# kitt_db01.net
KiCad netlist of a schematic drawn in EAGLE
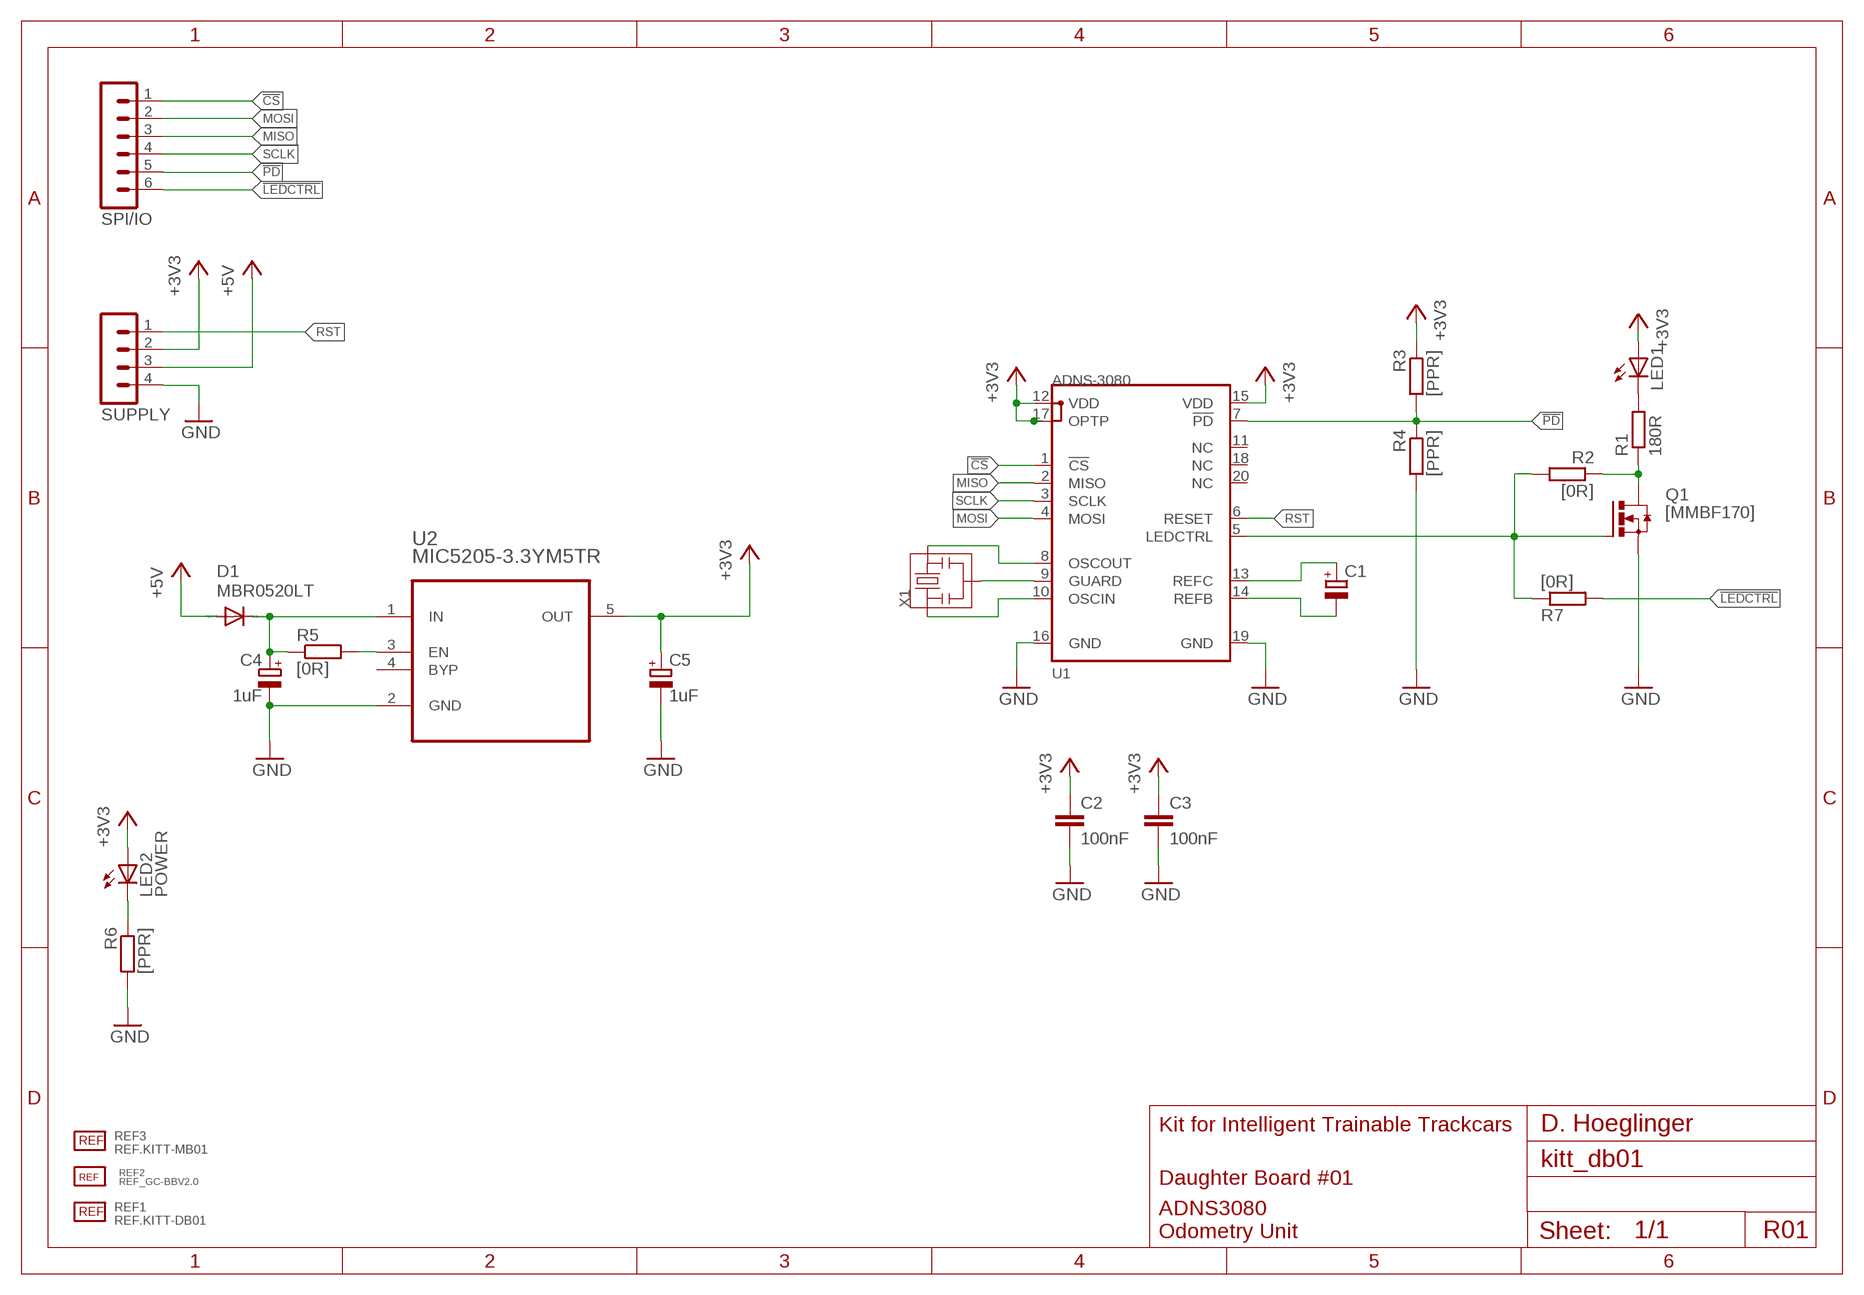
[diagram p0: schematic, sheet 1]

(export (version "E")
  (design (tool "Eeschema 10.0.6"))
  (components
    (comp (ref "C1")
      (value "CPOL-EUSMCB")
      (footprint "eagle-import:SMC_B")
      (libsource (lib "eagle-import") (part "CPOL-EUSMCB"))
    )
    (comp (ref "C2")
      (value "100nF")
      (footprint "eagle-import:C0805K")
      (libsource (lib "eagle-import") (part "C-EUC0805K"))
    )
    (comp (ref "C3")
      (value "100nF")
      (footprint "eagle-import:C0805K")
      (libsource (lib "eagle-import") (part "C-EUC0805K"))
    )
    (comp (ref "C4")
      (value "1uF")
      (footprint "eagle-import:A_3216-18W")
      (libsource (lib "eagle-import") (part "CPOL-EUA/3216-18W"))
    )
    (comp (ref "C5")
      (value "1uF")
      (footprint "eagle-import:A_3216-18W")
      (libsource (lib "eagle-import") (part "CPOL-EUA/3216-18W"))
    )
    (comp (ref "D1")
      (value "MBR0520LT")
      (footprint "eagle-import:SOD123")
      (libsource (lib "eagle-import") (part "MBR0520LT"))
    )
    (comp (ref "LED1")
      (value "LED5MM")
      (footprint "eagle-import:LED5MM")
      (libsource (lib "eagle-import") (part "LED5MM"))
    )
    (comp (ref "LED2")
      (value "POWER")
      (footprint "eagle-import:CHIP-LED0805")
      (libsource (lib "eagle-import") (part "LEDCHIP-LED0805"))
    )
    (comp (ref "Q1")
      (value "[MMBF170]")
      (footprint "eagle-import:SOT223")
      (libsource (lib "eagle-import") (part "N-HEXFET-2D_?-SOT232"))
    )
    (comp (ref "R1")
      (value "180R")
      (footprint "eagle-import:R0805")
      (libsource (lib "eagle-import") (part "R-EU_R0805"))
    )
    (comp (ref "R2")
      (value "[0R]")
      (footprint "eagle-import:R0805")
      (libsource (lib "eagle-import") (part "R-EU_R0805"))
    )
    (comp (ref "R3")
      (value "[PPR]")
      (footprint "eagle-import:R0805")
      (libsource (lib "eagle-import") (part "R-EU_R0805"))
    )
    (comp (ref "R4")
      (value "[PPR]")
      (footprint "eagle-import:R0805")
      (libsource (lib "eagle-import") (part "R-EU_R0805"))
    )
    (comp (ref "R5")
      (value "[0R]")
      (footprint "eagle-import:R0805")
      (libsource (lib "eagle-import") (part "R-EU_R0805"))
    )
    (comp (ref "R6")
      (value "[PPR]")
      (footprint "eagle-import:R0805")
      (libsource (lib "eagle-import") (part "R-EU_R0805"))
    )
    (comp (ref "R7")
      (value "[0R]")
      (footprint "eagle-import:R0805")
      (libsource (lib "eagle-import") (part "R-EU_R0805"))
    )
    (comp (ref "REF1")
      (value "REF.KITT-DB01")
      (footprint "eagle-import:REF_KITT-DB01")
      (libsource (lib "eagle-import") (part "REF.KITT-DB01"))
    )
    (comp (ref "REF2")
      (value "REF_GC-BBV2.0")
      (footprint "eagle-import:REF_GHOSTCAR")
      (libsource (lib "eagle-import") (part "REF_GC-BBV2.0"))
    )
    (comp (ref "REF3")
      (value "REF.KITT-MB01")
      (footprint "eagle-import:REF_KITT_MB01")
      (libsource (lib "eagle-import") (part "REF.KITT-MB01"))
    )
    (comp (ref "SPI/IO")
      (value "MA06-1")
      (footprint "eagle-import:MA06-1")
      (libsource (lib "eagle-import") (part "MA06-1"))
    )
    (comp (ref "SUPPLY")
      (value "MA04-1")
      (footprint "eagle-import:MA04-1")
      (libsource (lib "eagle-import") (part "MA04-1"))
    )
    (comp (ref "U1")
      (value "ADNS-3080")
      (footprint "eagle-import:ADNS-3080")
      (libsource (lib "eagle-import") (part "ADNS-3080"))
    )
    (comp (ref "U2")
      (value "MIC5205-3.3YM5TR")
      (footprint "eagle-import:SOT95P280X130-5N")
      (fields (field (name "MF") "Microchip") (field (name "MP") "MIC5205-3.3YM5-TR"))
      (libsource (lib "eagle-import") (part "MIC5205-3.3YM5TR"))
    )
    (comp (ref "X1")
      (value "RESON")
      (footprint "eagle-import:RESON-SMD")
      (libsource (lib "eagle-import") (part "RESON"))
    )
  )
  (nets
    (net (code "1") (name "+3V3") (class "Default")
      (node (ref "C2") (pin "1") (pinfunction "1_1") (pintype "passive"))
      (node (ref "C3") (pin "1") (pinfunction "1_1") (pintype "passive"))
      (node (ref "C5") (pin "+") (pinfunction "+_+") (pintype "passive"))
      (node (ref "LED1") (pin "A") (pinfunction "A_A") (pintype "passive"))
      (node (ref "LED2") (pin "A") (pinfunction "A_A") (pintype "passive"))
      (node (ref "R3") (pin "1") (pinfunction "1_1") (pintype "passive"))
      (node (ref "SUPPLY") (pin "2") (pinfunction "2_2") (pintype "passive"))
      (node (ref "U1") (pin "12") (pinfunction "VDD_12") (pintype "power_in"))
      (node (ref "U1") (pin "15") (pinfunction "VDD_15") (pintype "power_in"))
      (node (ref "U1") (pin "17") (pinfunction "OPTP_17") (pintype "open_collector"))
      (node (ref "U2") (pin "5") (pinfunction "OUT_5") (pintype "output"))
    )
    (net (code "2") (name "+5V") (class "Default")
      (node (ref "D1") (pin "A") (pinfunction "A_A") (pintype "passive"))
      (node (ref "SUPPLY") (pin "3") (pinfunction "3_3") (pintype "passive"))
    )
    (net (code "3") (name "/~{CS}") (class "Default")
      (node (ref "SPI/IO") (pin "1") (pinfunction "1_1") (pintype "passive"))
      (node (ref "U1") (pin "1") (pinfunction "~{CS}_1") (pintype "input"))
    )
    (net (code "4") (name "/~{LEDCTRL}") (class "Default")
      (node (ref "R7") (pin "2") (pinfunction "2_2") (pintype "passive"))
      (node (ref "SPI/IO") (pin "6") (pinfunction "6_6") (pintype "passive"))
    )
    (net (code "5") (name "/~{PD}") (class "Default")
      (node (ref "R3") (pin "2") (pinfunction "2_2") (pintype "passive"))
      (node (ref "R4") (pin "1") (pinfunction "1_1") (pintype "passive"))
      (node (ref "SPI/IO") (pin "5") (pinfunction "5_5") (pintype "passive"))
      (node (ref "U1") (pin "7") (pinfunction "~{PD}_7") (pintype "input"))
    )
    (net (code "6") (name "GND") (class "Default")
      (node (ref "C2") (pin "2") (pinfunction "2_2") (pintype "passive"))
      (node (ref "C3") (pin "2") (pinfunction "2_2") (pintype "passive"))
      (node (ref "C4") (pin "-") (pinfunction "-_-") (pintype "passive"))
      (node (ref "C5") (pin "-") (pinfunction "-_-") (pintype "passive"))
      (node (ref "Q1") (pin "3") (pinfunction "S_3") (pintype "passive"))
      (node (ref "R4") (pin "2") (pinfunction "2_2") (pintype "passive"))
      (node (ref "R6") (pin "2") (pinfunction "2_2") (pintype "passive"))
      (node (ref "SUPPLY") (pin "4") (pinfunction "4_4") (pintype "passive"))
      (node (ref "U1") (pin "16") (pinfunction "GND_16") (pintype "power_in"))
      (node (ref "U1") (pin "19") (pinfunction "GND_19") (pintype "power_in"))
      (node (ref "U2") (pin "2") (pinfunction "GND_2") (pintype "passive"))
    )
    (net (code "7") (name "MISO") (class "Default")
      (node (ref "SPI/IO") (pin "3") (pinfunction "3_3") (pintype "passive"))
      (node (ref "U1") (pin "2") (pinfunction "MISO_2") (pintype "output"))
    )
    (net (code "8") (name "MOSI") (class "Default")
      (node (ref "SPI/IO") (pin "2") (pinfunction "2_2") (pintype "passive"))
      (node (ref "U1") (pin "4") (pinfunction "MOSI_4") (pintype "input"))
    )
    (net (code "9") (name "Net-(LED1-C)") (class "Default")
      (node (ref "LED1") (pin "K") (pinfunction "C_K") (pintype "passive"))
      (node (ref "R1") (pin "2") (pinfunction "2_2") (pintype "passive"))
    )
    (net (code "10") (name "Net-(LED2-PadC)") (class "Default")
      (node (ref "LED2") (pin "C") (pinfunction "C_C") (pintype "passive"))
      (node (ref "R6") (pin "1") (pinfunction "1_1") (pintype "passive"))
    )
    (net (code "11") (name "Net-(Q1-D-Pad2)") (class "Default")
      (node (ref "Q1") (pin "2") (pinfunction "D_2") (pintype "passive"))
      (node (ref "Q1") (pin "4") (pinfunction "D_4") (pintype "passive"))
      (node (ref "R1") (pin "1") (pinfunction "1_1") (pintype "passive"))
      (node (ref "R2") (pin "1") (pinfunction "1_1") (pintype "passive"))
    )
    (net (code "12") (name "Net-(Q1-G)") (class "Default")
      (node (ref "Q1") (pin "1") (pinfunction "G_1") (pintype "passive"))
      (node (ref "R2") (pin "2") (pinfunction "2_2") (pintype "passive"))
      (node (ref "R7") (pin "1") (pinfunction "1_1") (pintype "passive"))
      (node (ref "U1") (pin "5") (pinfunction "LEDCTRL_5") (pintype "output"))
    )
    (net (code "13") (name "Net-(U1-GUARD)") (class "Default")
      (node (ref "U1") (pin "9") (pinfunction "GUARD_9") (pintype "power_in"))
      (node (ref "X1") (pin "2") (pinfunction "2_2") (pintype "passive"))
    )
    (net (code "14") (name "Net-(U1-OSCIN)") (class "Default")
      (node (ref "U1") (pin "10") (pinfunction "OSCIN_10") (pintype "input"))
      (node (ref "X1") (pin "1") (pinfunction "1_1") (pintype "passive"))
    )
    (net (code "15") (name "Net-(U1-OSCOUT)") (class "Default")
      (node (ref "U1") (pin "8") (pinfunction "OSCOUT_8") (pintype "output"))
      (node (ref "X1") (pin "3") (pinfunction "3_3") (pintype "passive"))
    )
    (net (code "16") (name "Net-(U1-REFB)") (class "Default")
      (node (ref "C1") (pin "-") (pinfunction "-_-") (pintype "passive"))
      (node (ref "U1") (pin "14") (pinfunction "REFB_14") (pintype "input"))
    )
    (net (code "17") (name "Net-(U1-REFC)") (class "Default")
      (node (ref "C1") (pin "+") (pinfunction "+_+") (pintype "passive"))
      (node (ref "U1") (pin "13") (pinfunction "REFC_13") (pintype "input"))
    )
    (net (code "18") (name "Net-(U2-EN)") (class "Default")
      (node (ref "R5") (pin "2") (pinfunction "2_2") (pintype "passive"))
      (node (ref "U2") (pin "3") (pinfunction "EN_3") (pintype "input"))
    )
    (net (code "19") (name "Net-(U2-IN)") (class "Default")
      (node (ref "C4") (pin "+") (pinfunction "+_+") (pintype "passive"))
      (node (ref "D1") (pin "C") (pinfunction "C_C") (pintype "passive"))
      (node (ref "R5") (pin "1") (pinfunction "1_1") (pintype "passive"))
      (node (ref "U2") (pin "1") (pinfunction "IN_1") (pintype "input"))
    )
    (net (code "20") (name "RST") (class "Default")
      (node (ref "SUPPLY") (pin "1") (pinfunction "1_1") (pintype "passive"))
      (node (ref "U1") (pin "6") (pinfunction "RESET_6") (pintype "input"))
    )
    (net (code "21") (name "SCLK") (class "Default")
      (node (ref "SPI/IO") (pin "4") (pinfunction "4_4") (pintype "passive"))
      (node (ref "U1") (pin "3") (pinfunction "SCLK_3") (pintype "input"))
    )
    (net (code "22") (name "unconnected-(U1-NC-Pad11)") (class "Default")
      (node (ref "U1") (pin "11") (pinfunction "NC_11") (pintype "no_connect"))
    )
    (net (code "23") (name "unconnected-(U1-NC-Pad18)") (class "Default")
      (node (ref "U1") (pin "18") (pinfunction "NC_18") (pintype "no_connect"))
    )
    (net (code "24") (name "unconnected-(U1-NC-Pad20)") (class "Default")
      (node (ref "U1") (pin "20") (pinfunction "NC_20") (pintype "no_connect"))
    )
    (net (code "25") (name "unconnected-(U2-BYP-Pad4)") (class "Default")
      (node (ref "U2") (pin "4") (pinfunction "BYP_4") (pintype "input"))
    )
  )
)
